# teenseyBreakoutFin.net
KiCad netlist of a schematic drawn in EAGLE
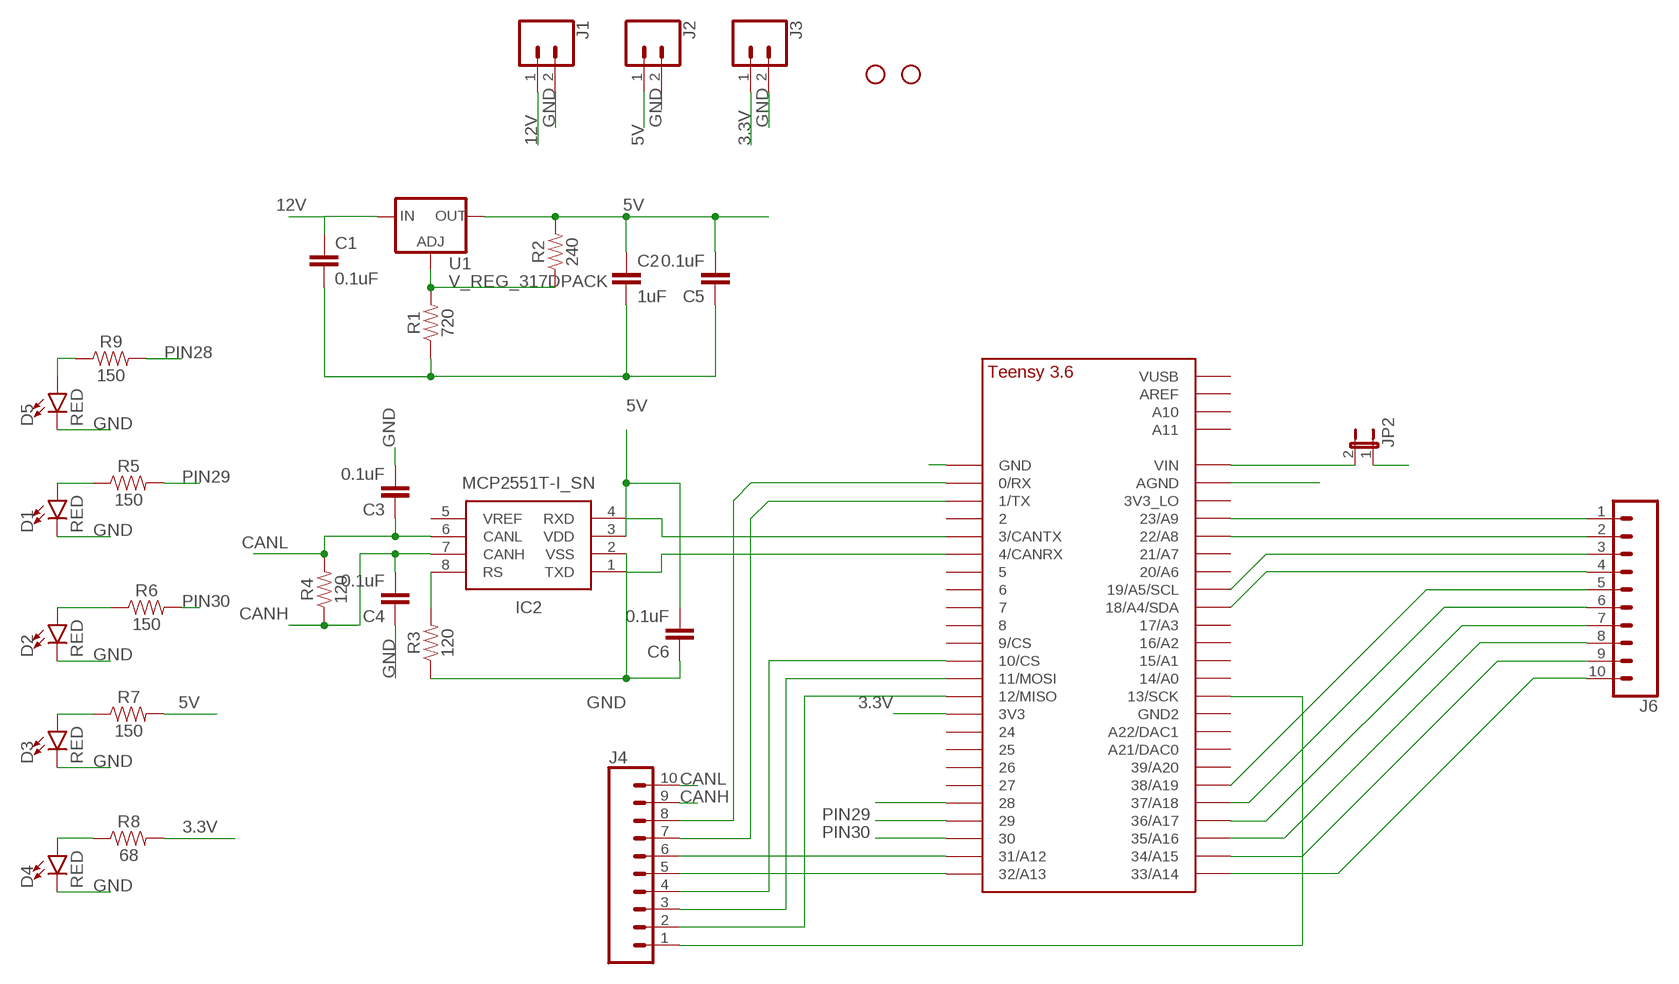
[diagram p0: schematic, sheet 1]

(export (version "E")
  (design (tool "Eeschema 10.0.6"))
  (components
    (comp (ref "C1")
      (value "0.1uF")
      (footprint "eagle-import:0402")
      (libsource (lib "eagle-import") (part "0.1UF-0402-16V-10%"))
    )
    (comp (ref "C2")
      (value "1uF")
      (footprint "eagle-import:0603")
      (libsource (lib "eagle-import") (part "0.22UF-0603-25V-10%"))
    )
    (comp (ref "C3")
      (value "0.1uF")
      (footprint "eagle-import:0603")
      (libsource (lib "eagle-import") (part "0.1UF-0603-25V-(+80/-20%)"))
    )
    (comp (ref "C4")
      (value "0.1uF")
      (footprint "eagle-import:0603")
      (libsource (lib "eagle-import") (part "0.1UF-0603-25V-(+80/-20%)"))
    )
    (comp (ref "C5")
      (value "0.1uF")
      (footprint "eagle-import:0603")
      (libsource (lib "eagle-import") (part "0.1UF-0603-25V-(+80/-20%)"))
    )
    (comp (ref "C6")
      (value "0.1uF")
      (footprint "eagle-import:0603")
      (libsource (lib "eagle-import") (part "0.1UF-0603-25V-(+80/-20%)"))
    )
    (comp (ref "D1")
      (value "RED")
      (footprint "eagle-import:LED-0603")
      (libsource (lib "eagle-import") (part "LED-RED0603"))
    )
    (comp (ref "D2")
      (value "RED")
      (footprint "eagle-import:LED-0603")
      (libsource (lib "eagle-import") (part "LED-RED0603"))
    )
    (comp (ref "D3")
      (value "RED")
      (footprint "eagle-import:LED-0603")
      (libsource (lib "eagle-import") (part "LED-RED0603"))
    )
    (comp (ref "D4")
      (value "RED")
      (footprint "eagle-import:LED-0603")
      (libsource (lib "eagle-import") (part "LED-RED0603"))
    )
    (comp (ref "D5")
      (value "RED")
      (footprint "eagle-import:LED-0603")
      (libsource (lib "eagle-import") (part "LED-RED0603"))
    )
    (comp (ref "H2")
      (value "STAND-OFF")
      (footprint "eagle-import:STAND-OFF")
      (libsource (lib "eagle-import") (part "STAND-OFF"))
    )
    (comp (ref "IC2")
      (value "MCP2551T-I_SN")
      (footprint "eagle-import:SOIC127P600X175-8N")
      (fields
        (field (name "MANUFACTURER_PART_NUMBER") "MCP2551T-I/SN")
        (field (name "RS_PART_NUMBER") "8237897P")
      )
      (libsource (lib "eagle-import") (part "MCP2551T-I_SN"))
    )
    (comp (ref "J1")
      (value "CONN_023.5MM_LOCK")
      (footprint "eagle-import:SCREWTERMINAL-3.5MM-2_LOCK")
      (libsource (lib "eagle-import") (part "CONN_023.5MM_LOCK"))
    )
    (comp (ref "J2")
      (value "CONN_023.5MM_LOCK")
      (footprint "eagle-import:SCREWTERMINAL-3.5MM-2_LOCK")
      (libsource (lib "eagle-import") (part "CONN_023.5MM_LOCK"))
    )
    (comp (ref "J3")
      (value "CONN_023.5MM_LOCK")
      (footprint "eagle-import:SCREWTERMINAL-3.5MM-2_LOCK")
      (libsource (lib "eagle-import") (part "CONN_023.5MM_LOCK"))
    )
    (comp (ref "J4")
      (value "CONN_10LOCK")
      (footprint "eagle-import:1X10_LOCK")
      (libsource (lib "eagle-import") (part "CONN_10LOCK"))
    )
    (comp (ref "J6")
      (value "CONN_10LOCK")
      (footprint "eagle-import:1X10_LOCK")
      (libsource (lib "eagle-import") (part "CONN_10LOCK"))
    )
    (comp (ref "JP2")
      (value "JP1E")
      (footprint "eagle-import:JP1")
      (libsource (lib "eagle-import") (part "JP1E"))
    )
    (comp (ref "R1")
      (value "720")
      (footprint "eagle-import:0603")
      (libsource (lib "eagle-import") (part "1.20KOHM-0603-1/10W-1%"))
    )
    (comp (ref "R2")
      (value "240")
      (footprint "eagle-import:0603")
      (libsource (lib "eagle-import") (part "1.20KOHM-0603-1/10W-1%"))
    )
    (comp (ref "R3")
      (value "120")
      (footprint "eagle-import:0603")
      (libsource (lib "eagle-import") (part "1.2MOHM-0603-1/10W-1%"))
    )
    (comp (ref "R4")
      (value "120")
      (footprint "eagle-import:AXIAL-0.3")
      (libsource (lib "eagle-import") (part "10KOHM-HORIZ-1/4W-1%"))
    )
    (comp (ref "R5")
      (value "150")
      (footprint "eagle-import:0603")
      (libsource (lib "eagle-import") (part "0.27OHM-0603-1/10W-1%"))
    )
    (comp (ref "R6")
      (value "150")
      (footprint "eagle-import:0603")
      (libsource (lib "eagle-import") (part "0.27OHM-0603-1/10W-1%"))
    )
    (comp (ref "R7")
      (value "150")
      (footprint "eagle-import:0603")
      (libsource (lib "eagle-import") (part "0.27OHM-0603-1/10W-1%"))
    )
    (comp (ref "R8")
      (value "68")
      (footprint "eagle-import:0603")
      (libsource (lib "eagle-import") (part "0.27OHM-0603-1/10W-1%"))
    )
    (comp (ref "R9")
      (value "150")
      (footprint "eagle-import:0603")
      (libsource (lib "eagle-import") (part "0.27OHM-0603-1/10W-1%"))
    )
    (comp (ref "SCREW_HOLE")
      (value "STAND-OFF")
      (footprint "eagle-import:STAND-OFF")
      (libsource (lib "eagle-import") (part "STAND-OFF"))
    )
    (comp (ref "U$1")
      (value "TEENSY_3.5/3.6_BASIC")
      (footprint "eagle-import:TEENSY_3.5_3.6_BASIC")
      (libsource (lib "eagle-import") (part "TEENSY_3.5/3.6_BASIC"))
    )
    (comp (ref "U1")
      (value "V_REG_317DPACK")
      (footprint "eagle-import:V-REG_DPACK")
      (libsource (lib "eagle-import") (part "V_REG_317DPACK"))
    )
  )
  (nets
    (net (code "1") (name "/3.3V") (class "Default")
      (node (ref "J3") (pin "1") (pinfunction "1_1") (pintype "passive"))
      (node (ref "R8") (pin "2") (pinfunction "2_2") (pintype "passive"))
      (node (ref "U$1") (pin "3V3") (pinfunction "3V3_3V3") (pintype "bidirectional"))
    )
    (net (code "2") (name "/5V") (class "Default")
      (node (ref "C2") (pin "1") (pinfunction "1_1") (pintype "passive"))
      (node (ref "C5") (pin "2") (pinfunction "2_2") (pintype "passive"))
      (node (ref "C6") (pin "2") (pinfunction "2_2") (pintype "passive"))
      (node (ref "IC2") (pin "3") (pinfunction "VDD_3") (pintype "power_in"))
      (node (ref "J2") (pin "1") (pinfunction "1_1") (pintype "passive"))
      (node (ref "JP2") (pin "1") (pinfunction "1_1") (pintype "passive"))
      (node (ref "R2") (pin "2") (pinfunction "2_2") (pintype "passive"))
      (node (ref "R7") (pin "2") (pinfunction "2_2") (pintype "passive"))
      (node (ref "U1") (pin "4") (pinfunction "OUT_4") (pintype "output"))
    )
    (net (code "3") (name "/12V") (class "Default")
      (node (ref "C1") (pin "1") (pinfunction "1_1") (pintype "passive"))
      (node (ref "J1") (pin "1") (pinfunction "1_1") (pintype "passive"))
      (node (ref "U1") (pin "3") (pinfunction "IN_3") (pintype "input"))
    )
    (net (code "4") (name "/CANH") (class "Default")
      (node (ref "C4") (pin "2") (pinfunction "2_2") (pintype "passive"))
      (node (ref "IC2") (pin "7") (pinfunction "CANH_7") (pintype "passive"))
      (node (ref "J4") (pin "9") (pinfunction "9_9") (pintype "passive"))
      (node (ref "R4") (pin "P$1") (pinfunction "1_P$1") (pintype "passive"))
    )
    (net (code "5") (name "/CANL") (class "Default")
      (node (ref "C3") (pin "1") (pinfunction "1_1") (pintype "passive"))
      (node (ref "IC2") (pin "6") (pinfunction "CANL_6") (pintype "passive"))
      (node (ref "J4") (pin "10") (pinfunction "10_10") (pintype "passive"))
      (node (ref "R4") (pin "P$2") (pinfunction "2_P$2") (pintype "passive"))
    )
    (net (code "6") (name "/GND") (class "Default")
      (node (ref "C1") (pin "2") (pinfunction "2_2") (pintype "passive"))
      (node (ref "C2") (pin "2") (pinfunction "2_2") (pintype "passive"))
      (node (ref "C3") (pin "2") (pinfunction "2_2") (pintype "passive"))
      (node (ref "C4") (pin "1") (pinfunction "1_1") (pintype "passive"))
      (node (ref "C5") (pin "1") (pinfunction "1_1") (pintype "passive"))
      (node (ref "C6") (pin "1") (pinfunction "1_1") (pintype "passive"))
      (node (ref "D1") (pin "C") (pinfunction "C_C") (pintype "passive"))
      (node (ref "D2") (pin "C") (pinfunction "C_C") (pintype "passive"))
      (node (ref "D3") (pin "C") (pinfunction "C_C") (pintype "passive"))
      (node (ref "D4") (pin "C") (pinfunction "C_C") (pintype "passive"))
      (node (ref "D5") (pin "C") (pinfunction "C_C") (pintype "passive"))
      (node (ref "IC2") (pin "2") (pinfunction "VSS_2") (pintype "power_in"))
      (node (ref "J1") (pin "2") (pinfunction "2_2") (pintype "passive"))
      (node (ref "J2") (pin "2") (pinfunction "2_2") (pintype "passive"))
      (node (ref "J3") (pin "2") (pinfunction "2_2") (pintype "passive"))
      (node (ref "R1") (pin "1") (pinfunction "1_1") (pintype "passive"))
      (node (ref "R3") (pin "1") (pinfunction "1_1") (pintype "passive"))
      (node (ref "U$1") (pin "AGND") (pinfunction "AGND_AGND") (pintype "bidirectional"))
      (node (ref "U$1") (pin "GND") (pinfunction "GND_GND") (pintype "bidirectional"))
    )
    (net (code "7") (name "/PIN28") (class "Default")
      (node (ref "R9") (pin "2") (pinfunction "2_2") (pintype "passive"))
      (node (ref "U$1") (pin "28") (pinfunction "28_28") (pintype "bidirectional"))
    )
    (net (code "8") (name "/PIN29") (class "Default")
      (node (ref "R5") (pin "2") (pinfunction "2_2") (pintype "passive"))
      (node (ref "U$1") (pin "29") (pinfunction "29_29") (pintype "bidirectional"))
    )
    (net (code "9") (name "/PIN30") (class "Default")
      (node (ref "R6") (pin "2") (pinfunction "2_2") (pintype "passive"))
      (node (ref "U$1") (pin "30") (pinfunction "30_30") (pintype "bidirectional"))
    )
    (net (code "10") (name "Net-(D1-PadA)") (class "Default")
      (node (ref "D1") (pin "A") (pinfunction "A_A") (pintype "passive"))
      (node (ref "R5") (pin "1") (pinfunction "1_1") (pintype "passive"))
    )
    (net (code "11") (name "Net-(D2-PadA)") (class "Default")
      (node (ref "D2") (pin "A") (pinfunction "A_A") (pintype "passive"))
      (node (ref "R6") (pin "1") (pinfunction "1_1") (pintype "passive"))
    )
    (net (code "12") (name "Net-(D3-PadA)") (class "Default")
      (node (ref "D3") (pin "A") (pinfunction "A_A") (pintype "passive"))
      (node (ref "R7") (pin "1") (pinfunction "1_1") (pintype "passive"))
    )
    (net (code "13") (name "Net-(D4-PadA)") (class "Default")
      (node (ref "D4") (pin "A") (pinfunction "A_A") (pintype "passive"))
      (node (ref "R8") (pin "1") (pinfunction "1_1") (pintype "passive"))
    )
    (net (code "14") (name "Net-(D5-PadA)") (class "Default")
      (node (ref "D5") (pin "A") (pinfunction "A_A") (pintype "passive"))
      (node (ref "R9") (pin "1") (pinfunction "1_1") (pintype "passive"))
    )
    (net (code "15") (name "Net-(IC2-RS)") (class "Default")
      (node (ref "IC2") (pin "8") (pinfunction "RS_8") (pintype "passive"))
      (node (ref "R3") (pin "2") (pinfunction "2_2") (pintype "passive"))
    )
    (net (code "16") (name "Net-(IC2-RXD)") (class "Default")
      (node (ref "IC2") (pin "4") (pinfunction "RXD_4") (pintype "passive"))
      (node (ref "U$1") (pin "3/CANTX") (pinfunction "3/CANTX_3/CANTX") (pintype "bidirectional"))
    )
    (net (code "17") (name "Net-(IC2-TXD)") (class "Default")
      (node (ref "IC2") (pin "1") (pinfunction "TXD_1") (pintype "passive"))
      (node (ref "U$1") (pin "4/CANRX") (pinfunction "4/CANRX_4/CANRX") (pintype "bidirectional"))
    )
    (net (code "18") (name "Net-(J4-Pad1)") (class "Default")
      (node (ref "J4") (pin "1") (pinfunction "1_1") (pintype "passive"))
      (node (ref "U$1") (pin "13/SCK") (pinfunction "13/SCK_13/SCK") (pintype "bidirectional"))
    )
    (net (code "19") (name "Net-(J4-Pad2)") (class "Default")
      (node (ref "J4") (pin "2") (pinfunction "2_2") (pintype "passive"))
      (node (ref "U$1") (pin "12/MISO") (pinfunction "12/MISO_12/MISO") (pintype "bidirectional"))
    )
    (net (code "20") (name "Net-(J4-Pad3)") (class "Default")
      (node (ref "J4") (pin "3") (pinfunction "3_3") (pintype "passive"))
      (node (ref "U$1") (pin "11/MOSI") (pinfunction "11/MOSI_11/MOSI") (pintype "bidirectional"))
    )
    (net (code "21") (name "Net-(J4-Pad4)") (class "Default")
      (node (ref "J4") (pin "4") (pinfunction "4_4") (pintype "passive"))
      (node (ref "U$1") (pin "10/CS") (pinfunction "10/CS_10/CS") (pintype "bidirectional"))
    )
    (net (code "22") (name "Net-(J4-Pad5)") (class "Default")
      (node (ref "J4") (pin "5") (pinfunction "5_5") (pintype "passive"))
      (node (ref "U$1") (pin "32/A13") (pinfunction "32/A13_32/A13") (pintype "bidirectional"))
    )
    (net (code "23") (name "Net-(J4-Pad6)") (class "Default")
      (node (ref "J4") (pin "6") (pinfunction "6_6") (pintype "passive"))
      (node (ref "U$1") (pin "31/A12") (pinfunction "31/A12_31/A12") (pintype "bidirectional"))
    )
    (net (code "24") (name "Net-(J4-Pad7)") (class "Default")
      (node (ref "J4") (pin "7") (pinfunction "7_7") (pintype "passive"))
      (node (ref "U$1") (pin "1/TX") (pinfunction "1/TX_1/TX") (pintype "bidirectional"))
    )
    (net (code "25") (name "Net-(J4-Pad8)") (class "Default")
      (node (ref "J4") (pin "8") (pinfunction "8_8") (pintype "passive"))
      (node (ref "U$1") (pin "0/RX") (pinfunction "0/RX_0/RX") (pintype "bidirectional"))
    )
    (net (code "26") (name "Net-(J6-Pad1)") (class "Default")
      (node (ref "J6") (pin "1") (pinfunction "1_1") (pintype "passive"))
      (node (ref "U$1") (pin "23/A9") (pinfunction "23/A9_23/A9") (pintype "bidirectional"))
    )
    (net (code "27") (name "Net-(J6-Pad2)") (class "Default")
      (node (ref "J6") (pin "2") (pinfunction "2_2") (pintype "passive"))
      (node (ref "U$1") (pin "22/A8") (pinfunction "22/A8_22/A8") (pintype "bidirectional"))
    )
    (net (code "28") (name "Net-(J6-Pad3)") (class "Default")
      (node (ref "J6") (pin "3") (pinfunction "3_3") (pintype "passive"))
      (node (ref "U$1") (pin "19/A5/SCL") (pinfunction "19/A5/SCL_19/A5/SCL") (pintype "bidirectional"))
    )
    (net (code "29") (name "Net-(J6-Pad4)") (class "Default")
      (node (ref "J6") (pin "4") (pinfunction "4_4") (pintype "passive"))
      (node (ref "U$1") (pin "18/A4/SDA") (pinfunction "18/A4/SDA_18/A4/SDA") (pintype "bidirectional"))
    )
    (net (code "30") (name "Net-(J6-Pad5)") (class "Default")
      (node (ref "J6") (pin "5") (pinfunction "5_5") (pintype "passive"))
      (node (ref "U$1") (pin "38/A19") (pinfunction "38/A19_38/A19") (pintype "bidirectional"))
    )
    (net (code "31") (name "Net-(J6-Pad6)") (class "Default")
      (node (ref "J6") (pin "6") (pinfunction "6_6") (pintype "passive"))
      (node (ref "U$1") (pin "37/A18") (pinfunction "37/A18_37/A18") (pintype "bidirectional"))
    )
    (net (code "32") (name "Net-(J6-Pad7)") (class "Default")
      (node (ref "J6") (pin "7") (pinfunction "7_7") (pintype "passive"))
      (node (ref "U$1") (pin "36/A17") (pinfunction "36/A17_36/A17") (pintype "bidirectional"))
    )
    (net (code "33") (name "Net-(J6-Pad8)") (class "Default")
      (node (ref "J6") (pin "8") (pinfunction "8_8") (pintype "passive"))
      (node (ref "U$1") (pin "35/A16") (pinfunction "35/A16_35/A16") (pintype "bidirectional"))
    )
    (net (code "34") (name "Net-(J6-Pad9)") (class "Default")
      (node (ref "J6") (pin "9") (pinfunction "9_9") (pintype "passive"))
      (node (ref "U$1") (pin "34/A15") (pinfunction "34/A15_34/A15") (pintype "bidirectional"))
    )
    (net (code "35") (name "Net-(J6-Pad10)") (class "Default")
      (node (ref "J6") (pin "10") (pinfunction "10_10") (pintype "passive"))
      (node (ref "U$1") (pin "33/A14") (pinfunction "33/A14_33/A14") (pintype "bidirectional"))
    )
    (net (code "36") (name "Net-(JP2-Pad2)") (class "Default")
      (node (ref "JP2") (pin "2") (pinfunction "2_2") (pintype "passive"))
      (node (ref "U$1") (pin "VIN") (pinfunction "VIN_VIN") (pintype "bidirectional"))
    )
    (net (code "37") (name "Net-(U1-ADJ)") (class "Default")
      (node (ref "R1") (pin "2") (pinfunction "2_2") (pintype "passive"))
      (node (ref "R2") (pin "1") (pinfunction "1_1") (pintype "passive"))
      (node (ref "U1") (pin "1") (pinfunction "ADJ_1") (pintype "input"))
    )
    (net (code "38") (name "unconnected-(IC2-VREF-Pad5)") (class "Default")
      (node (ref "IC2") (pin "5") (pinfunction "VREF_5") (pintype "input"))
    )
    (net (code "39") (name "unconnected-(U$1-A21{slash}DAC0-Pad21{slash}DAC0)") (class "Default")
      (node (ref "U$1") (pin "21/DAC0") (pinfunction "A21/DAC0_21/DAC0") (pintype "bidirectional"))
    )
    (net (code "40") (name "unconnected-(U$1-Pad2)") (class "Default")
      (node (ref "U$1") (pin "2") (pinfunction "2_2") (pintype "bidirectional"))
    )
    (net (code "41") (name "unconnected-(U$1-Pad3V3_LO)") (class "Default")
      (node (ref "U$1") (pin "3V3_LO") (pinfunction "3V3_LO_3V3_LO") (pintype "bidirectional"))
    )
    (net (code "42") (name "unconnected-(U$1-Pad5)") (class "Default")
      (node (ref "U$1") (pin "5") (pinfunction "5_5") (pintype "bidirectional"))
    )
    (net (code "43") (name "unconnected-(U$1-Pad6)") (class "Default")
      (node (ref "U$1") (pin "6") (pinfunction "6_6") (pintype "bidirectional"))
    )
    (net (code "44") (name "unconnected-(U$1-Pad7)") (class "Default")
      (node (ref "U$1") (pin "7") (pinfunction "7_7") (pintype "bidirectional"))
    )
    (net (code "45") (name "unconnected-(U$1-Pad8)") (class "Default")
      (node (ref "U$1") (pin "8") (pinfunction "8_8") (pintype "bidirectional"))
    )
    (net (code "46") (name "unconnected-(U$1-Pad9{slash}CS)") (class "Default")
      (node (ref "U$1") (pin "9/CS") (pinfunction "9/CS_9/CS") (pintype "bidirectional"))
    )
    (net (code "47") (name "unconnected-(U$1-Pad14{slash}A0)") (class "Default")
      (node (ref "U$1") (pin "14/A0") (pinfunction "14/A0_14/A0") (pintype "bidirectional"))
    )
    (net (code "48") (name "unconnected-(U$1-Pad15{slash}A1)") (class "Default")
      (node (ref "U$1") (pin "15/A1") (pinfunction "15/A1_15/A1") (pintype "bidirectional"))
    )
    (net (code "49") (name "unconnected-(U$1-Pad16{slash}A2)") (class "Default")
      (node (ref "U$1") (pin "16/A2") (pinfunction "16/A2_16/A2") (pintype "bidirectional"))
    )
    (net (code "50") (name "unconnected-(U$1-Pad17{slash}A3)") (class "Default")
      (node (ref "U$1") (pin "17/A3") (pinfunction "17/A3_17/A3") (pintype "bidirectional"))
    )
    (net (code "51") (name "unconnected-(U$1-Pad20{slash}A6)") (class "Default")
      (node (ref "U$1") (pin "20/A6") (pinfunction "20/A6_20/A6") (pintype "bidirectional"))
    )
    (net (code "52") (name "unconnected-(U$1-Pad21{slash}A7)") (class "Default")
      (node (ref "U$1") (pin "21/A7") (pinfunction "21/A7_21/A7") (pintype "bidirectional"))
    )
    (net (code "53") (name "unconnected-(U$1-Pad24)") (class "Default")
      (node (ref "U$1") (pin "24") (pinfunction "24_24") (pintype "bidirectional"))
    )
    (net (code "54") (name "unconnected-(U$1-Pad25)") (class "Default")
      (node (ref "U$1") (pin "25") (pinfunction "25_25") (pintype "bidirectional"))
    )
    (net (code "55") (name "unconnected-(U$1-Pad26)") (class "Default")
      (node (ref "U$1") (pin "26") (pinfunction "26_26") (pintype "bidirectional"))
    )
    (net (code "56") (name "unconnected-(U$1-Pad27)") (class "Default")
      (node (ref "U$1") (pin "27") (pinfunction "27_27") (pintype "bidirectional"))
    )
    (net (code "57") (name "unconnected-(U$1-Pad39{slash}A20)") (class "Default")
      (node (ref "U$1") (pin "39/A20") (pinfunction "39/A20_39/A20") (pintype "bidirectional"))
    )
    (net (code "58") (name "unconnected-(U$1-PadA10)") (class "Default")
      (node (ref "U$1") (pin "A10") (pinfunction "A10_A10") (pintype "bidirectional"))
    )
    (net (code "59") (name "unconnected-(U$1-PadA11)") (class "Default")
      (node (ref "U$1") (pin "A11") (pinfunction "A11_A11") (pintype "bidirectional"))
    )
    (net (code "60") (name "unconnected-(U$1-PadA22{slash}DAC1)") (class "Default")
      (node (ref "U$1") (pin "A22/DAC1") (pinfunction "A22/DAC1_A22/DAC1") (pintype "bidirectional"))
    )
    (net (code "61") (name "unconnected-(U$1-PadAREF)") (class "Default")
      (node (ref "U$1") (pin "AREF") (pinfunction "AREF_AREF") (pintype "bidirectional"))
    )
    (net (code "62") (name "unconnected-(U$1-PadGND2)") (class "Default")
      (node (ref "U$1") (pin "GND2") (pinfunction "GND2_GND2") (pintype "bidirectional"))
    )
    (net (code "63") (name "unconnected-(U$1-PadVUSB)") (class "Default")
      (node (ref "U$1") (pin "VUSB") (pinfunction "VUSB_VUSB") (pintype "bidirectional"))
    )
  )
)
